# Microcontroleur_Affichage.net
KiCad netlist of a schematic drawn in Altium Designer
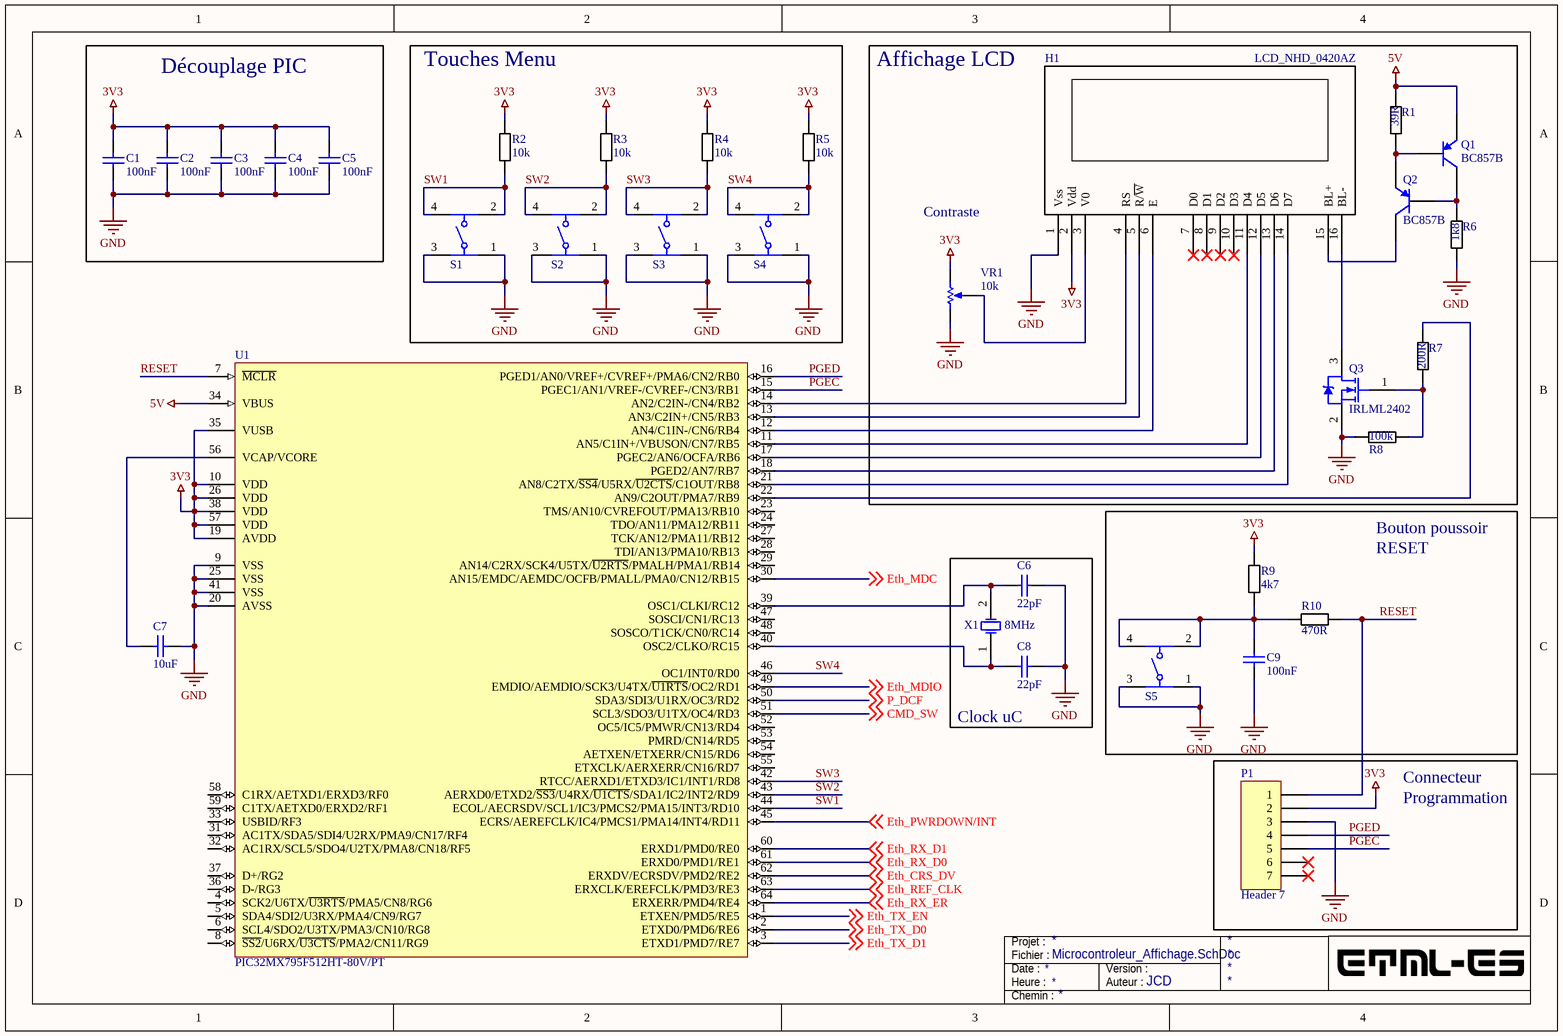
[diagram p0: Microcontroleur_Affichage.SchDoc]

(export (version "E")
  (design (tool "Eeschema 10.0.6"))
  (components
    (comp (ref "C1")
      (value "100nF")
      (footprint "C0805")
      (description "Capacitor")
      (fields (field (name "PUBLISHER") "Altium Limited"))
      (libsource (lib "Miscellaneous Devices") (part "Cap"))
    )
    (comp (ref "C2")
      (value "100nF")
      (footprint "C0805")
      (description "Capacitor")
      (fields (field (name "PUBLISHER") "Altium Limited"))
      (libsource (lib "Miscellaneous Devices") (part "Cap"))
    )
    (comp (ref "C3")
      (value "100nF")
      (footprint "C0805")
      (description "Capacitor")
      (fields (field (name "PUBLISHER") "Altium Limited"))
      (libsource (lib "Miscellaneous Devices") (part "Cap"))
    )
    (comp (ref "C4")
      (value "100nF")
      (footprint "C0805")
      (description "Capacitor")
      (fields (field (name "PUBLISHER") "Altium Limited"))
      (libsource (lib "Miscellaneous Devices") (part "Cap"))
    )
    (comp (ref "C5")
      (value "100nF")
      (footprint "C0805")
      (description "Capacitor")
      (fields (field (name "PUBLISHER") "Altium Limited"))
      (libsource (lib "Miscellaneous Devices") (part "Cap"))
    )
    (comp (ref "C6")
      (value "22pF")
      (footprint "C0805")
      (description "Capacitor")
      (fields (field (name "PUBLISHER") "Altium Limited"))
      (libsource (lib "Miscellaneous Devices") (part "Cap"))
    )
    (comp (ref "C7")
      (value "10uF")
      (footprint "C0805")
      (description "Capacitor")
      (fields (field (name "PUBLISHER") "Altium Limited"))
      (libsource (lib "Miscellaneous Devices") (part "Cap"))
    )
    (comp (ref "C8")
      (value "22pF")
      (footprint "C0805")
      (description "Capacitor")
      (fields (field (name "PUBLISHER") "Altium Limited"))
      (libsource (lib "Miscellaneous Devices") (part "Cap"))
    )
    (comp (ref "C9")
      (value "100nF")
      (footprint "C0805")
      (description "Capacitor")
      (fields (field (name "PUBLISHER") "Altium Limited"))
      (libsource (lib "Miscellaneous Devices") (part "Cap"))
    )
    (comp (ref "H1")
      (value "LCD_NHD_0420AZ")
      (footprint "NHD-0420AZ-FSW-GBW-33V3")
      (libsource (lib "LibComposant1819") (part "NHD-0420AZ-FSW-GBW-33V3"))
    )
    (comp (ref "P1")
      (value "Header 7")
      (footprint "HDR1X7")
      (description "Header, 7-Pin")
      (fields (field (name "PUBLISHER") "Altium Limited"))
      (libsource (lib "Miscellaneous Connectors") (part "Header 7"))
    )
    (comp (ref "Q1")
      (value "BC857B")
      (footprint "INF-SOT23_L")
      (description "PNP Silicon AF Transistor, 45 V VCEO, 100 mA IC, SOT23, Reel, Green")
      (fields (field (name "MANUFACTURER") "Infineon"))
      (libsource (lib "Altium Content Vault") (part "INF-BJTPNP-BEC-3"))
    )
    (comp (ref "Q2")
      (value "BC857B")
      (footprint "INF-SOT23_L")
      (description "PNP Silicon AF Transistor, 45 V VCEO, 100 mA IC, SOT23, Reel, Green")
      (fields (field (name "MANUFACTURER") "Infineon"))
      (libsource (lib "Altium Content Vault") (part "INF-BJTPNP-BEC-3"))
    )
    (comp (ref "Q3")
      (value "IRLML2402")
      (footprint "INTR-IRLML2402TRPBF-3_V")
      (description "HEXFET(R) Power MOSFET, N-Channel, 20 V, 1.2 A, 3-Pin SOT-23, RoHS, Tape and Reel")
      (fields (field (name "MANUFACTURER") "International Rectifier"))
      (libsource (lib "Altium Content Vault") (part "NEMOS-GSD-3_A"))
    )
    (comp (ref "R1") (value "39R") (footprint "RESC0805(2012)_L") (libsource (lib "") (part "Resistance_2")))
    (comp (ref "R2") (value "10k") (footprint "RESC0805(2012)_L") (libsource (lib "") (part "Resistance_1")))
    (comp (ref "R3") (value "10k") (footprint "RESC0805(2012)_L") (libsource (lib "") (part "Resistance_1")))
    (comp (ref "R4") (value "10k") (footprint "RESC0805(2012)_L") (libsource (lib "") (part "Resistance_1")))
    (comp (ref "R5") (value "10k") (footprint "RESC0805(2012)_L") (libsource (lib "") (part "Resistance_1")))
    (comp (ref "R6") (value "1k8") (footprint "RESC0805(2012)_L") (libsource (lib "") (part "Resistance_2")))
    (comp (ref "R7") (value "200R") (footprint "RESC0805(2012)_L") (libsource (lib "") (part "Resistance_2")))
    (comp (ref "R8")
      (value "100k")
      (footprint "RESC0805(2012)_L")
      (libsource (lib "LibComposant1819") (part "Resistance"))
    )
    (comp (ref "R9") (value "4k7") (footprint "RESC0805(2012)_L") (libsource (lib "") (part "Resistance_1")))
    (comp (ref "R10")
      (value "470R")
      (footprint "RESC0805(2012)_L")
      (libsource (lib "LibComposant1819") (part "Resistance"))
    )
    (comp (ref "S1")
      (value "430152095836")
      (footprint "430152095836")
      (description "6x6mm SMD Tact Switch WS-TASV, height 9.5 mm, 360 gf")
      (fields (field (name "PUBLISHER") "Wurth Elektronik"))
      (libsource (lib "ALTIUM-WS-TASV-rev17b") (part "430152095836"))
    )
    (comp (ref "S2")
      (value "430152095836")
      (footprint "430152095836")
      (description "6x6mm SMD Tact Switch WS-TASV, height 9.5 mm, 360 gf")
      (fields (field (name "PUBLISHER") "Wurth Elektronik"))
      (libsource (lib "ALTIUM-WS-TASV-rev17b") (part "430152095836"))
    )
    (comp (ref "S3")
      (value "430152095836")
      (footprint "430152095836")
      (description "6x6mm SMD Tact Switch WS-TASV, height 9.5 mm, 360 gf")
      (fields (field (name "PUBLISHER") "Wurth Elektronik"))
      (libsource (lib "ALTIUM-WS-TASV-rev17b") (part "430152095836"))
    )
    (comp (ref "S4")
      (value "430152095836")
      (footprint "430152095836")
      (description "6x6mm SMD Tact Switch WS-TASV, height 9.5 mm, 360 gf")
      (fields (field (name "PUBLISHER") "Wurth Elektronik"))
      (libsource (lib "ALTIUM-WS-TASV-rev17b") (part "430152095836"))
    )
    (comp (ref "S5")
      (value "430152043836")
      (footprint "430152043836")
      (description "6x6mm SMD Tact Switch WS-TASV, height 4.3 mm, 360 gf")
      (fields (field (name "PUBLISHER") "Wurth Elektronik"))
      (libsource (lib "ALTIUM-WS-TASV-rev17b") (part "430152043836"))
    )
    (comp (ref "U1")
      (value "PIC32MX795F512HT-80V/PT")
      (footprint "TQFP-PT64_L")
      (libsource (lib "Altium Content Vault") (part "MC-32B-MX795-SQ64"))
    )
    (comp (ref "VR1")
      (value "10k")
      (footprint "BOUR-3362P")
      (description "Square Trimpot(R) Trimming Potentiometer, 10 KOhm, 300 V, -55 to 125 degC, 3-Pin THD, RoHS, Tube")
      (fields (field (name "TOLERANCE") "1%"))
      (libsource (lib "Altium Content Vault") (part "RES-POT-3"))
    )
    (comp (ref "X1")
      (value "8MHz")
      (footprint "ECS-80-18-5PX-TR_V")
      (description "Low Profile Quartz Crystal, 8.0 MHz, 2-Pin SMD, RoHS, Tape and Reel")
      (fields (field (name "TOLERANCE") "30PPM") (field (name "MANUFACTURER") "ECS"))
      (libsource (lib "Altium Content Vault") (part "XTAL_1-2-2"))
    )
  )
  (nets
    (net (code "1") (name "/PGEC") (class "Default")
      (node (ref "P1") (pin "5") (pinfunction "5_5") (pintype "passive"))
      (node (ref "U1") (pin "15") (pinfunction "PGEC1/AN1/VREF-/CVREF-/CN3/RB1_15") (pintype "bidirectional"))
    )
    (net (code "2") (name "/PGED") (class "Default")
      (node (ref "P1") (pin "4") (pinfunction "4_4") (pintype "passive"))
      (node (ref "U1") (pin "16") (pinfunction "PGED1/AN0/VREF+/CVREF+/PMA6/CN2/RB0_16") (pintype "bidirectional"))
    )
    (net (code "3") (name "/RESET") (class "Default")
      (node (ref "P1") (pin "1") (pinfunction "1_1") (pintype "passive"))
      (node (ref "R10") (pin "2") (pinfunction "2_2") (pintype "passive"))
      (node (ref "U1") (pin "7") (pinfunction "~{MCLR}_7") (pintype "input"))
    )
    (net (code "4") (name "/SW1") (class "Default")
      (node (ref "R2") (pin "2") (pinfunction "2_2") (pintype "passive"))
      (node (ref "S1") (pin "2") (pinfunction "2_2") (pintype "passive"))
      (node (ref "S1") (pin "4") (pinfunction "4_4") (pintype "passive"))
      (node (ref "U1") (pin "44") (pinfunction "ECOL/AECRSDV/SCL1/IC3/PMCS2/PMA15/INT3/RD10_44") (pintype "bidirectional"))
    )
    (net (code "5") (name "/SW2") (class "Default")
      (node (ref "R3") (pin "2") (pinfunction "2_2") (pintype "passive"))
      (node (ref "S2") (pin "2") (pinfunction "2_2") (pintype "passive"))
      (node (ref "S2") (pin "4") (pinfunction "4_4") (pintype "passive"))
      (node (ref "U1") (pin "43") (pinfunction "AERXD0/ETXD2/~{SS3}/U4RX/~{U1CTS}/SDA1/IC2/INT2/RD9_43") (pintype "bidirectional"))
    )
    (net (code "6") (name "/SW3") (class "Default")
      (node (ref "R4") (pin "2") (pinfunction "2_2") (pintype "passive"))
      (node (ref "S3") (pin "2") (pinfunction "2_2") (pintype "passive"))
      (node (ref "S3") (pin "4") (pinfunction "4_4") (pintype "passive"))
      (node (ref "U1") (pin "42") (pinfunction "RTCC/AERXD1/ETXD3/IC1/INT1/RD8_42") (pintype "bidirectional"))
    )
    (net (code "7") (name "/SW4") (class "Default")
      (node (ref "R5") (pin "2") (pinfunction "2_2") (pintype "passive"))
      (node (ref "S4") (pin "2") (pinfunction "2_2") (pintype "passive"))
      (node (ref "S4") (pin "4") (pinfunction "4_4") (pintype "passive"))
      (node (ref "U1") (pin "46") (pinfunction "OC1/INT0/RD0_46") (pintype "bidirectional"))
    )
    (net (code "8") (name "3V3") (class "Default")
      (node (ref "C1") (pin "2") (pinfunction "2_2") (pintype "passive"))
      (node (ref "C2") (pin "2") (pinfunction "2_2") (pintype "passive"))
      (node (ref "C3") (pin "2") (pinfunction "2_2") (pintype "passive"))
      (node (ref "C4") (pin "2") (pinfunction "2_2") (pintype "passive"))
      (node (ref "C5") (pin "2") (pinfunction "2_2") (pintype "passive"))
      (node (ref "H1") (pin "2") (pinfunction "Vdd_2") (pintype "passive"))
      (node (ref "P1") (pin "2") (pinfunction "2_2") (pintype "passive"))
      (node (ref "R2") (pin "1") (pinfunction "1_1") (pintype "passive"))
      (node (ref "R3") (pin "1") (pinfunction "1_1") (pintype "passive"))
      (node (ref "R4") (pin "1") (pinfunction "1_1") (pintype "passive"))
      (node (ref "R5") (pin "1") (pinfunction "1_1") (pintype "passive"))
      (node (ref "R9") (pin "1") (pinfunction "1_1") (pintype "passive"))
      (node (ref "U1") (pin "10") (pinfunction "VDD_10") (pintype "power_in"))
      (node (ref "U1") (pin "19") (pinfunction "AVDD_19") (pintype "power_in"))
      (node (ref "U1") (pin "26") (pinfunction "VDD_26") (pintype "power_in"))
      (node (ref "U1") (pin "35") (pinfunction "VUSB_35") (pintype "power_in"))
      (node (ref "U1") (pin "38") (pinfunction "VDD_38") (pintype "power_in"))
      (node (ref "U1") (pin "57") (pinfunction "VDD_57") (pintype "power_in"))
      (node (ref "VR1") (pin "3") (pinfunction "CW_3") (pintype "passive"))
    )
    (net (code "9") (name "5V") (class "Default")
      (node (ref "Q1") (pin "2") (pinfunction "E_2") (pintype "passive"))
      (node (ref "R1") (pin "2") (pinfunction "2_2") (pintype "passive"))
      (node (ref "U1") (pin "34") (pinfunction "VBUS_34") (pintype "input"))
    )
    (net (code "10") (name "CMD_SW") (class "Default")
      (node (ref "U1") (pin "51") (pinfunction "SCL3/SDO3/U1TX/OC4/RD3_51") (pintype "bidirectional"))
    )
    (net (code "11") (name "Eth_CRS_DV") (class "Default")
      (node (ref "U1") (pin "62") (pinfunction "ERXDV/ECRSDV/PMD2/RE2_62") (pintype "bidirectional"))
    )
    (net (code "12") (name "Eth_MDC") (class "Default")
      (node (ref "U1") (pin "30") (pinfunction "AN15/EMDC/AEMDC/OCFB/PMALL/PMA0/CN12/RB15_30") (pintype "bidirectional"))
    )
    (net (code "13") (name "Eth_MDIO") (class "Default")
      (node (ref "U1") (pin "49") (pinfunction "EMDIO/AEMDIO/SCK3/U4TX/~{U1RTS}/OC2/RD1_49") (pintype "bidirectional"))
    )
    (net (code "14") (name "Eth_PWRDOWN{slash}INT") (class "Default")
      (node (ref "U1") (pin "45") (pinfunction "ECRS/AEREFCLK/IC4/PMCS1/PMA14/INT4/RD11_45") (pintype "bidirectional"))
    )
    (net (code "15") (name "Eth_REF_CLK") (class "Default")
      (node (ref "U1") (pin "63") (pinfunction "ERXCLK/EREFCLK/PMD3/RE3_63") (pintype "bidirectional"))
    )
    (net (code "16") (name "Eth_RX_D0") (class "Default")
      (node (ref "U1") (pin "61") (pinfunction "ERXD0/PMD1/RE1_61") (pintype "bidirectional"))
    )
    (net (code "17") (name "Eth_RX_D1") (class "Default")
      (node (ref "U1") (pin "60") (pinfunction "ERXD1/PMD0/RE0_60") (pintype "bidirectional"))
    )
    (net (code "18") (name "Eth_RX_ER") (class "Default")
      (node (ref "U1") (pin "64") (pinfunction "ERXERR/PMD4/RE4_64") (pintype "bidirectional"))
    )
    (net (code "19") (name "Eth_TX_D0") (class "Default")
      (node (ref "U1") (pin "2") (pinfunction "ETXD0/PMD6/RE6_2") (pintype "bidirectional"))
    )
    (net (code "20") (name "Eth_TX_D1") (class "Default")
      (node (ref "U1") (pin "3") (pinfunction "ETXD1/PMD7/RE7_3") (pintype "bidirectional"))
    )
    (net (code "21") (name "Eth_TX_EN") (class "Default")
      (node (ref "U1") (pin "1") (pinfunction "ETXEN/PMD5/RE5_1") (pintype "bidirectional"))
    )
    (net (code "22") (name "GND") (class "Default")
      (node (ref "C1") (pin "1") (pinfunction "1_1") (pintype "passive"))
      (node (ref "C2") (pin "1") (pinfunction "1_1") (pintype "passive"))
      (node (ref "C3") (pin "1") (pinfunction "1_1") (pintype "passive"))
      (node (ref "C4") (pin "1") (pinfunction "1_1") (pintype "passive"))
      (node (ref "C5") (pin "1") (pinfunction "1_1") (pintype "passive"))
      (node (ref "C6") (pin "2") (pinfunction "2_2") (pintype "passive"))
      (node (ref "C7") (pin "2") (pinfunction "2_2") (pintype "passive"))
      (node (ref "C8") (pin "2") (pinfunction "2_2") (pintype "passive"))
      (node (ref "C9") (pin "1") (pinfunction "1_1") (pintype "passive"))
      (node (ref "H1") (pin "1") (pinfunction "Vss_1") (pintype "passive"))
      (node (ref "P1") (pin "3") (pinfunction "3_3") (pintype "passive"))
      (node (ref "Q3") (pin "2") (pinfunction "S_2") (pintype "passive"))
      (node (ref "R6") (pin "1") (pinfunction "1_1") (pintype "passive"))
      (node (ref "R8") (pin "1") (pinfunction "1_1") (pintype "passive"))
      (node (ref "S1") (pin "1") (pinfunction "1_1") (pintype "passive"))
      (node (ref "S1") (pin "3") (pinfunction "3_3") (pintype "passive"))
      (node (ref "S2") (pin "1") (pinfunction "1_1") (pintype "passive"))
      (node (ref "S2") (pin "3") (pinfunction "3_3") (pintype "passive"))
      (node (ref "S3") (pin "1") (pinfunction "1_1") (pintype "passive"))
      (node (ref "S3") (pin "3") (pinfunction "3_3") (pintype "passive"))
      (node (ref "S4") (pin "1") (pinfunction "1_1") (pintype "passive"))
      (node (ref "S4") (pin "3") (pinfunction "3_3") (pintype "passive"))
      (node (ref "S5") (pin "1") (pinfunction "1_1") (pintype "passive"))
      (node (ref "S5") (pin "3") (pinfunction "3_3") (pintype "passive"))
      (node (ref "U1") (pin "20") (pinfunction "AVSS_20") (pintype "power_in"))
      (node (ref "U1") (pin "25") (pinfunction "VSS_25") (pintype "power_in"))
      (node (ref "U1") (pin "41") (pinfunction "VSS_41") (pintype "power_in"))
      (node (ref "U1") (pin "9") (pinfunction "VSS_9") (pintype "power_in"))
      (node (ref "VR1") (pin "1") (pinfunction "CCW_1") (pintype "passive"))
    )
    (net (code "23") (name "Net-(C9-Pad2)") (class "Default")
      (node (ref "C9") (pin "2") (pinfunction "2_2") (pintype "passive"))
      (node (ref "R10") (pin "1") (pinfunction "1_1") (pintype "passive"))
      (node (ref "R9") (pin "2") (pinfunction "2_2") (pintype "passive"))
      (node (ref "S5") (pin "2") (pinfunction "2_2") (pintype "passive"))
      (node (ref "S5") (pin "4") (pinfunction "4_4") (pintype "passive"))
    )
    (net (code "24") (name "Net-(H1-BL+)") (class "Default")
      (node (ref "H1") (pin "15") (pinfunction "BL+_15") (pintype "passive"))
      (node (ref "Q2") (pin "3") (pinfunction "C_3") (pintype "passive"))
    )
    (net (code "25") (name "Net-(H1-BL-)") (class "Default")
      (node (ref "H1") (pin "16") (pinfunction "BL-_16") (pintype "passive"))
      (node (ref "Q3") (pin "3") (pinfunction "D_3") (pintype "passive"))
    )
    (net (code "26") (name "Net-(H1-D4)") (class "Default")
      (node (ref "H1") (pin "11") (pinfunction "D4_11") (pintype "passive"))
      (node (ref "U1") (pin "11") (pinfunction "AN5/C1IN+/VBUSON/CN7/RB5_11") (pintype "bidirectional"))
    )
    (net (code "27") (name "Net-(H1-D5)") (class "Default")
      (node (ref "H1") (pin "12") (pinfunction "D5_12") (pintype "passive"))
      (node (ref "U1") (pin "17") (pinfunction "PGEC2/AN6/OCFA/RB6_17") (pintype "bidirectional"))
    )
    (net (code "28") (name "Net-(H1-D6)") (class "Default")
      (node (ref "H1") (pin "13") (pinfunction "D6_13") (pintype "passive"))
      (node (ref "U1") (pin "18") (pinfunction "PGED2/AN7/RB7_18") (pintype "bidirectional"))
    )
    (net (code "29") (name "Net-(H1-D7)") (class "Default")
      (node (ref "H1") (pin "14") (pinfunction "D7_14") (pintype "passive"))
      (node (ref "U1") (pin "21") (pinfunction "AN8/C2TX/~{SS4}/U5RX/~{U2CTS}/C1OUT/RB8_21") (pintype "bidirectional"))
    )
    (net (code "30") (name "Net-(H1-E)") (class "Default")
      (node (ref "H1") (pin "6") (pinfunction "E_6") (pintype "passive"))
      (node (ref "U1") (pin "12") (pinfunction "AN4/C1IN-/CN6/RB4_12") (pintype "bidirectional"))
    )
    (net (code "31") (name "Net-(H1-RS)") (class "Default")
      (node (ref "H1") (pin "4") (pinfunction "RS_4") (pintype "passive"))
      (node (ref "U1") (pin "14") (pinfunction "AN2/C2IN-/CN4/RB2_14") (pintype "bidirectional"))
    )
    (net (code "32") (name "Net-(H1-R{slash}~{W})") (class "Default")
      (node (ref "H1") (pin "5") (pinfunction "R/~{W}_5") (pintype "passive"))
      (node (ref "U1") (pin "13") (pinfunction "AN3/C2IN+/CN5/RB3_13") (pintype "bidirectional"))
    )
    (net (code "33") (name "Net-(H1-V0)") (class "Default")
      (node (ref "H1") (pin "3") (pinfunction "V0_3") (pintype "passive"))
      (node (ref "VR1") (pin "2") (pinfunction "S_2") (pintype "passive"))
    )
    (net (code "34") (name "Net-(Q1-B)") (class "Default")
      (node (ref "Q1") (pin "1") (pinfunction "B_1") (pintype "passive"))
      (node (ref "Q2") (pin "2") (pinfunction "E_2") (pintype "passive"))
      (node (ref "R1") (pin "1") (pinfunction "1_1") (pintype "passive"))
    )
    (net (code "35") (name "Net-(Q1-C)") (class "Default")
      (node (ref "Q1") (pin "3") (pinfunction "C_3") (pintype "passive"))
      (node (ref "Q2") (pin "1") (pinfunction "B_1") (pintype "passive"))
      (node (ref "R6") (pin "2") (pinfunction "2_2") (pintype "passive"))
    )
    (net (code "36") (name "Net-(Q3-G)") (class "Default")
      (node (ref "Q3") (pin "1") (pinfunction "G_1") (pintype "passive"))
      (node (ref "R7") (pin "1") (pinfunction "1_1") (pintype "passive"))
      (node (ref "R8") (pin "2") (pinfunction "2_2") (pintype "passive"))
    )
    (net (code "37") (name "Net-(U1-AN9{slash}C2OUT{slash}PMA7{slash}RB9)") (class "Default")
      (node (ref "R7") (pin "2") (pinfunction "2_2") (pintype "passive"))
      (node (ref "U1") (pin "22") (pinfunction "AN9/C2OUT/PMA7/RB9_22") (pintype "bidirectional"))
    )
    (net (code "38") (name "Net-(U1-OSC1{slash}CLKI{slash}RC12)") (class "Default")
      (node (ref "C6") (pin "1") (pinfunction "1_1") (pintype "passive"))
      (node (ref "U1") (pin "39") (pinfunction "OSC1/CLKI/RC12_39") (pintype "bidirectional"))
      (node (ref "X1") (pin "2") (pinfunction "X2_2") (pintype "passive"))
    )
    (net (code "39") (name "Net-(U1-OSC2{slash}CLKO{slash}RC15)") (class "Default")
      (node (ref "C8") (pin "1") (pinfunction "1_1") (pintype "passive"))
      (node (ref "U1") (pin "40") (pinfunction "OSC2/CLKO/RC15_40") (pintype "bidirectional"))
      (node (ref "X1") (pin "1") (pinfunction "X1_1") (pintype "passive"))
    )
    (net (code "40") (name "Net-(U1-VCAP{slash}VCORE)") (class "Default")
      (node (ref "C7") (pin "1") (pinfunction "1_1") (pintype "passive"))
      (node (ref "U1") (pin "56") (pinfunction "VCAP/VCORE_56") (pintype "power_in"))
    )
    (net (code "41") (name "P_DCF") (class "Default")
      (node (ref "U1") (pin "50") (pinfunction "SDA3/SDI3/U1RX/OC3/RD2_50") (pintype "bidirectional"))
    )
    (net (code "42") (name "unconnected-(H1-D0-Pad7)") (class "Default")
      (node (ref "H1") (pin "7") (pinfunction "D0_7") (pintype "passive+no_connect"))
    )
    (net (code "43") (name "unconnected-(H1-D1-Pad8)") (class "Default")
      (node (ref "H1") (pin "8") (pinfunction "D1_8") (pintype "passive+no_connect"))
    )
    (net (code "44") (name "unconnected-(H1-D2-Pad9)") (class "Default")
      (node (ref "H1") (pin "9") (pinfunction "D2_9") (pintype "passive+no_connect"))
    )
    (net (code "45") (name "unconnected-(H1-D3-Pad10)") (class "Default")
      (node (ref "H1") (pin "10") (pinfunction "D3_10") (pintype "passive+no_connect"))
    )
    (net (code "46") (name "unconnected-(P1-Pad6)") (class "Default")
      (node (ref "P1") (pin "6") (pinfunction "6_6") (pintype "passive+no_connect"))
    )
    (net (code "47") (name "unconnected-(P1-Pad7)") (class "Default")
      (node (ref "P1") (pin "7") (pinfunction "7_7") (pintype "passive+no_connect"))
    )
    (net (code "48") (name "unconnected-(U1-AC1RX{slash}SCL5{slash}SDO4{slash}U2TX{slash}PMA8{slash}CN18{slash}RF5-Pad32)") (class "Default")
      (node (ref "U1") (pin "32") (pinfunction "AC1RX/SCL5/SDO4/U2TX/PMA8/CN18/RF5_32") (pintype "bidirectional"))
    )
    (net (code "49") (name "unconnected-(U1-AC1TX{slash}SDA5{slash}SDI4{slash}U2RX{slash}PMA9{slash}CN17{slash}RF4-Pad31)") (class "Default")
      (node (ref "U1") (pin "31") (pinfunction "AC1TX/SDA5/SDI4/U2RX/PMA9/CN17/RF4_31") (pintype "bidirectional"))
    )
    (net (code "50") (name "unconnected-(U1-AETXEN{slash}ETXERR{slash}CN15{slash}RD6-Pad54)") (class "Default")
      (node (ref "U1") (pin "54") (pinfunction "AETXEN/ETXERR/CN15/RD6_54") (pintype "bidirectional"))
    )
    (net (code "51") (name "unconnected-(U1-AN14{slash}C2RX{slash}SCK4{slash}U5TX{slash}~{U2RTS}{slash}PMALH{slash}PMA1{slash}RB14-Pad29)") (class "Default")
      (node (ref "U1") (pin "29") (pinfunction "AN14/C2RX/SCK4/U5TX/~{U2RTS}/PMALH/PMA1/RB14_29") (pintype "bidirectional"))
    )
    (net (code "52") (name "unconnected-(U1-C1RX{slash}AETXD1{slash}ERXD3{slash}RF0-Pad58)") (class "Default")
      (node (ref "U1") (pin "58") (pinfunction "C1RX/AETXD1/ERXD3/RF0_58") (pintype "bidirectional"))
    )
    (net (code "53") (name "unconnected-(U1-C1TX{slash}AETXD0{slash}ERXD2{slash}RF1-Pad59)") (class "Default")
      (node (ref "U1") (pin "59") (pinfunction "C1TX/AETXD0/ERXD2/RF1_59") (pintype "bidirectional"))
    )
    (net (code "54") (name "unconnected-(U1-D+{slash}RG2-Pad37)") (class "Default")
      (node (ref "U1") (pin "37") (pinfunction "D+/RG2_37") (pintype "bidirectional"))
    )
    (net (code "55") (name "unconnected-(U1-D-{slash}RG3-Pad36)") (class "Default")
      (node (ref "U1") (pin "36") (pinfunction "D-/RG3_36") (pintype "bidirectional"))
    )
    (net (code "56") (name "unconnected-(U1-ETXCLK{slash}AERXERR{slash}CN16{slash}RD7-Pad55)") (class "Default")
      (node (ref "U1") (pin "55") (pinfunction "ETXCLK/AERXERR/CN16/RD7_55") (pintype "bidirectional"))
    )
    (net (code "57") (name "unconnected-(U1-OC5{slash}IC5{slash}PMWR{slash}CN13{slash}RD4-Pad52)") (class "Default")
      (node (ref "U1") (pin "52") (pinfunction "OC5/IC5/PMWR/CN13/RD4_52") (pintype "bidirectional"))
    )
    (net (code "58") (name "unconnected-(U1-PMRD{slash}CN14{slash}RD5-Pad53)") (class "Default")
      (node (ref "U1") (pin "53") (pinfunction "PMRD/CN14/RD5_53") (pintype "bidirectional"))
    )
    (net (code "59") (name "unconnected-(U1-SCK2{slash}U6TX{slash}~{U3RTS}{slash}PMA5{slash}CN8{slash}RG6-Pad4)") (class "Default")
      (node (ref "U1") (pin "4") (pinfunction "SCK2/U6TX/~{U3RTS}/PMA5/CN8/RG6_4") (pintype "bidirectional"))
    )
    (net (code "60") (name "unconnected-(U1-SCL4{slash}SDO2{slash}U3TX{slash}PMA3{slash}CN10{slash}RG8-Pad6)") (class "Default")
      (node (ref "U1") (pin "6") (pinfunction "SCL4/SDO2/U3TX/PMA3/CN10/RG8_6") (pintype "bidirectional"))
    )
    (net (code "61") (name "unconnected-(U1-SDA4{slash}SDI2{slash}U3RX{slash}PMA4{slash}CN9{slash}RG7-Pad5)") (class "Default")
      (node (ref "U1") (pin "5") (pinfunction "SDA4/SDI2/U3RX/PMA4/CN9/RG7_5") (pintype "bidirectional"))
    )
    (net (code "62") (name "unconnected-(U1-SOSCI{slash}CN1{slash}RC13-Pad47)") (class "Default")
      (node (ref "U1") (pin "47") (pinfunction "SOSCI/CN1/RC13_47") (pintype "bidirectional"))
    )
    (net (code "63") (name "unconnected-(U1-SOSCO{slash}T1CK{slash}CN0{slash}RC14-Pad48)") (class "Default")
      (node (ref "U1") (pin "48") (pinfunction "SOSCO/T1CK/CN0/RC14_48") (pintype "bidirectional"))
    )
    (net (code "64") (name "unconnected-(U1-TCK{slash}AN12{slash}PMA11{slash}RB12-Pad27)") (class "Default")
      (node (ref "U1") (pin "27") (pinfunction "TCK/AN12/PMA11/RB12_27") (pintype "bidirectional"))
    )
    (net (code "65") (name "unconnected-(U1-TDI{slash}AN13{slash}PMA10{slash}RB13-Pad28)") (class "Default")
      (node (ref "U1") (pin "28") (pinfunction "TDI/AN13/PMA10/RB13_28") (pintype "bidirectional"))
    )
    (net (code "66") (name "unconnected-(U1-TDO{slash}AN11{slash}PMA12{slash}RB11-Pad24)") (class "Default")
      (node (ref "U1") (pin "24") (pinfunction "TDO/AN11/PMA12/RB11_24") (pintype "bidirectional"))
    )
    (net (code "67") (name "unconnected-(U1-TMS{slash}AN10{slash}CVREFOUT{slash}PMA13{slash}RB10-Pad23)") (class "Default")
      (node (ref "U1") (pin "23") (pinfunction "TMS/AN10/CVREFOUT/PMA13/RB10_23") (pintype "bidirectional"))
    )
    (net (code "68") (name "unconnected-(U1-USBID{slash}RF3-Pad33)") (class "Default")
      (node (ref "U1") (pin "33") (pinfunction "USBID/RF3_33") (pintype "bidirectional"))
    )
    (net (code "69") (name "unconnected-(U1-~{SS2}{slash}U6RX{slash}~{U3CTS}{slash}PMA2{slash}CN11{slash}RG9-Pad8)") (class "Default")
      (node (ref "U1") (pin "8") (pinfunction "~{SS2}/U6RX/~{U3CTS}/PMA2/CN11/RG9_8") (pintype "bidirectional"))
    )
  )
)
